# APDS-9200.net
KiCad netlist of a schematic drawn in EAGLE
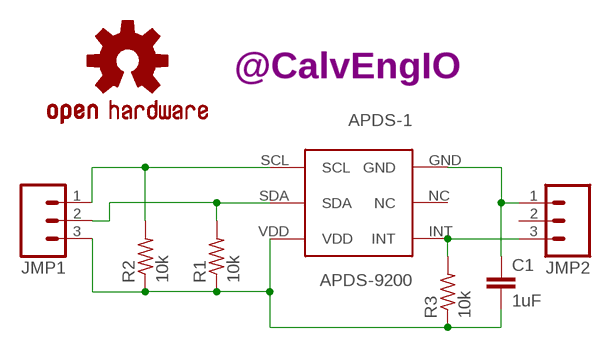
[diagram p0: schematic, sheet 1]

(export (version "E")
  (design (tool "Eeschema 10.0.6"))
  (components
    (comp (ref "APDS-1")
      (value "APDS-9200")
      (footprint "eagle-import:APDS-9200")
      (libsource (lib "eagle-import") (part "APDS-9200"))
    )
    (comp (ref "C1")
      (value "1uF")
      (footprint "eagle-import:C0402")
      (libsource (lib "eagle-import") (part "CAPACITOR0402"))
    )
    (comp (ref "JMP1")
      (value "JMP-03")
      (footprint "eagle-import:1X03")
      (libsource (lib "eagle-import") (part "JMP-03"))
    )
    (comp (ref "JMP2")
      (value "JMP-03")
      (footprint "eagle-import:1X03")
      (libsource (lib "eagle-import") (part "JMP-03"))
    )
    (comp (ref "LOGO1")
      (value "OSHW-LOGOMINI")
      (footprint "eagle-import:OSHW-LOGO-MINI")
      (libsource (lib "eagle-import") (part "OSHW-LOGOMINI"))
    )
    (comp (ref "R1")
      (value "10k")
      (footprint "eagle-import:R0402")
      (libsource (lib "eagle-import") (part "RESISTOR0402"))
    )
    (comp (ref "R2")
      (value "10k")
      (footprint "eagle-import:R0402")
      (libsource (lib "eagle-import") (part "RESISTOR0402"))
    )
    (comp (ref "R3")
      (value "10k")
      (footprint "eagle-import:R0402")
      (libsource (lib "eagle-import") (part "RESISTOR0402"))
    )
    (comp (ref "U$1")
      (value "CALVENGIO_HANDLEHANDLE.025")
      (footprint "eagle-import:CALVENGIO_HANDLE.025")
      (libsource (lib "eagle-import") (part "CALVENGIO_HANDLEHANDLE.025"))
    )
  )
  (nets
    (net (code "1") (name "Net-(JMP1-2)") (class "Default")
      (node (ref "APDS-1") (pin "SCL") (pinfunction "SCL_SCL") (pintype "bidirectional"))
      (node (ref "JMP1") (pin "1") (pinfunction "2_1") (pintype "passive"))
      (node (ref "R2") (pin "2") (pinfunction "2_2") (pintype "passive"))
    )
    (net (code "2") (name "Net-(JMP1-3)") (class "Default")
      (node (ref "APDS-1") (pin "SDA") (pinfunction "SDA_SDA") (pintype "bidirectional"))
      (node (ref "JMP1") (pin "2") (pinfunction "3_2") (pintype "passive"))
      (node (ref "R1") (pin "2") (pinfunction "2_2") (pintype "passive"))
    )
    (net (code "3") (name "Net-(JMP1-4)") (class "Default")
      (node (ref "APDS-1") (pin "VDD") (pinfunction "VDD_VDD") (pintype "bidirectional"))
      (node (ref "C1") (pin "2") (pinfunction "2_2") (pintype "passive"))
      (node (ref "JMP1") (pin "3") (pinfunction "4_3") (pintype "passive"))
      (node (ref "R1") (pin "1") (pinfunction "1_1") (pintype "passive"))
      (node (ref "R2") (pin "1") (pinfunction "1_1") (pintype "passive"))
      (node (ref "R3") (pin "1") (pinfunction "1_1") (pintype "passive"))
    )
    (net (code "4") (name "Net-(JMP2-2)") (class "Default")
      (node (ref "APDS-1") (pin "GND") (pinfunction "GND_GND") (pintype "bidirectional"))
      (node (ref "C1") (pin "1") (pinfunction "1_1") (pintype "passive"))
      (node (ref "JMP2") (pin "1") (pinfunction "2_1") (pintype "passive"))
    )
    (net (code "5") (name "Net-(JMP2-4)") (class "Default")
      (node (ref "APDS-1") (pin "INT") (pinfunction "INT_INT") (pintype "bidirectional"))
      (node (ref "JMP2") (pin "3") (pinfunction "4_3") (pintype "passive"))
      (node (ref "R3") (pin "2") (pinfunction "2_2") (pintype "passive"))
    )
    (net (code "6") (name "unconnected-(APDS-1-PadNC)") (class "Default")
      (node (ref "APDS-1") (pin "NC") (pinfunction "NC_NC") (pintype "bidirectional"))
    )
    (net (code "7") (name "unconnected-(JMP2-3-Pad2)") (class "Default")
      (node (ref "JMP2") (pin "2") (pinfunction "3_2") (pintype "passive"))
    )
  )
)
